# common_board_smd.net
KiCad netlist of a schematic drawn in EAGLE
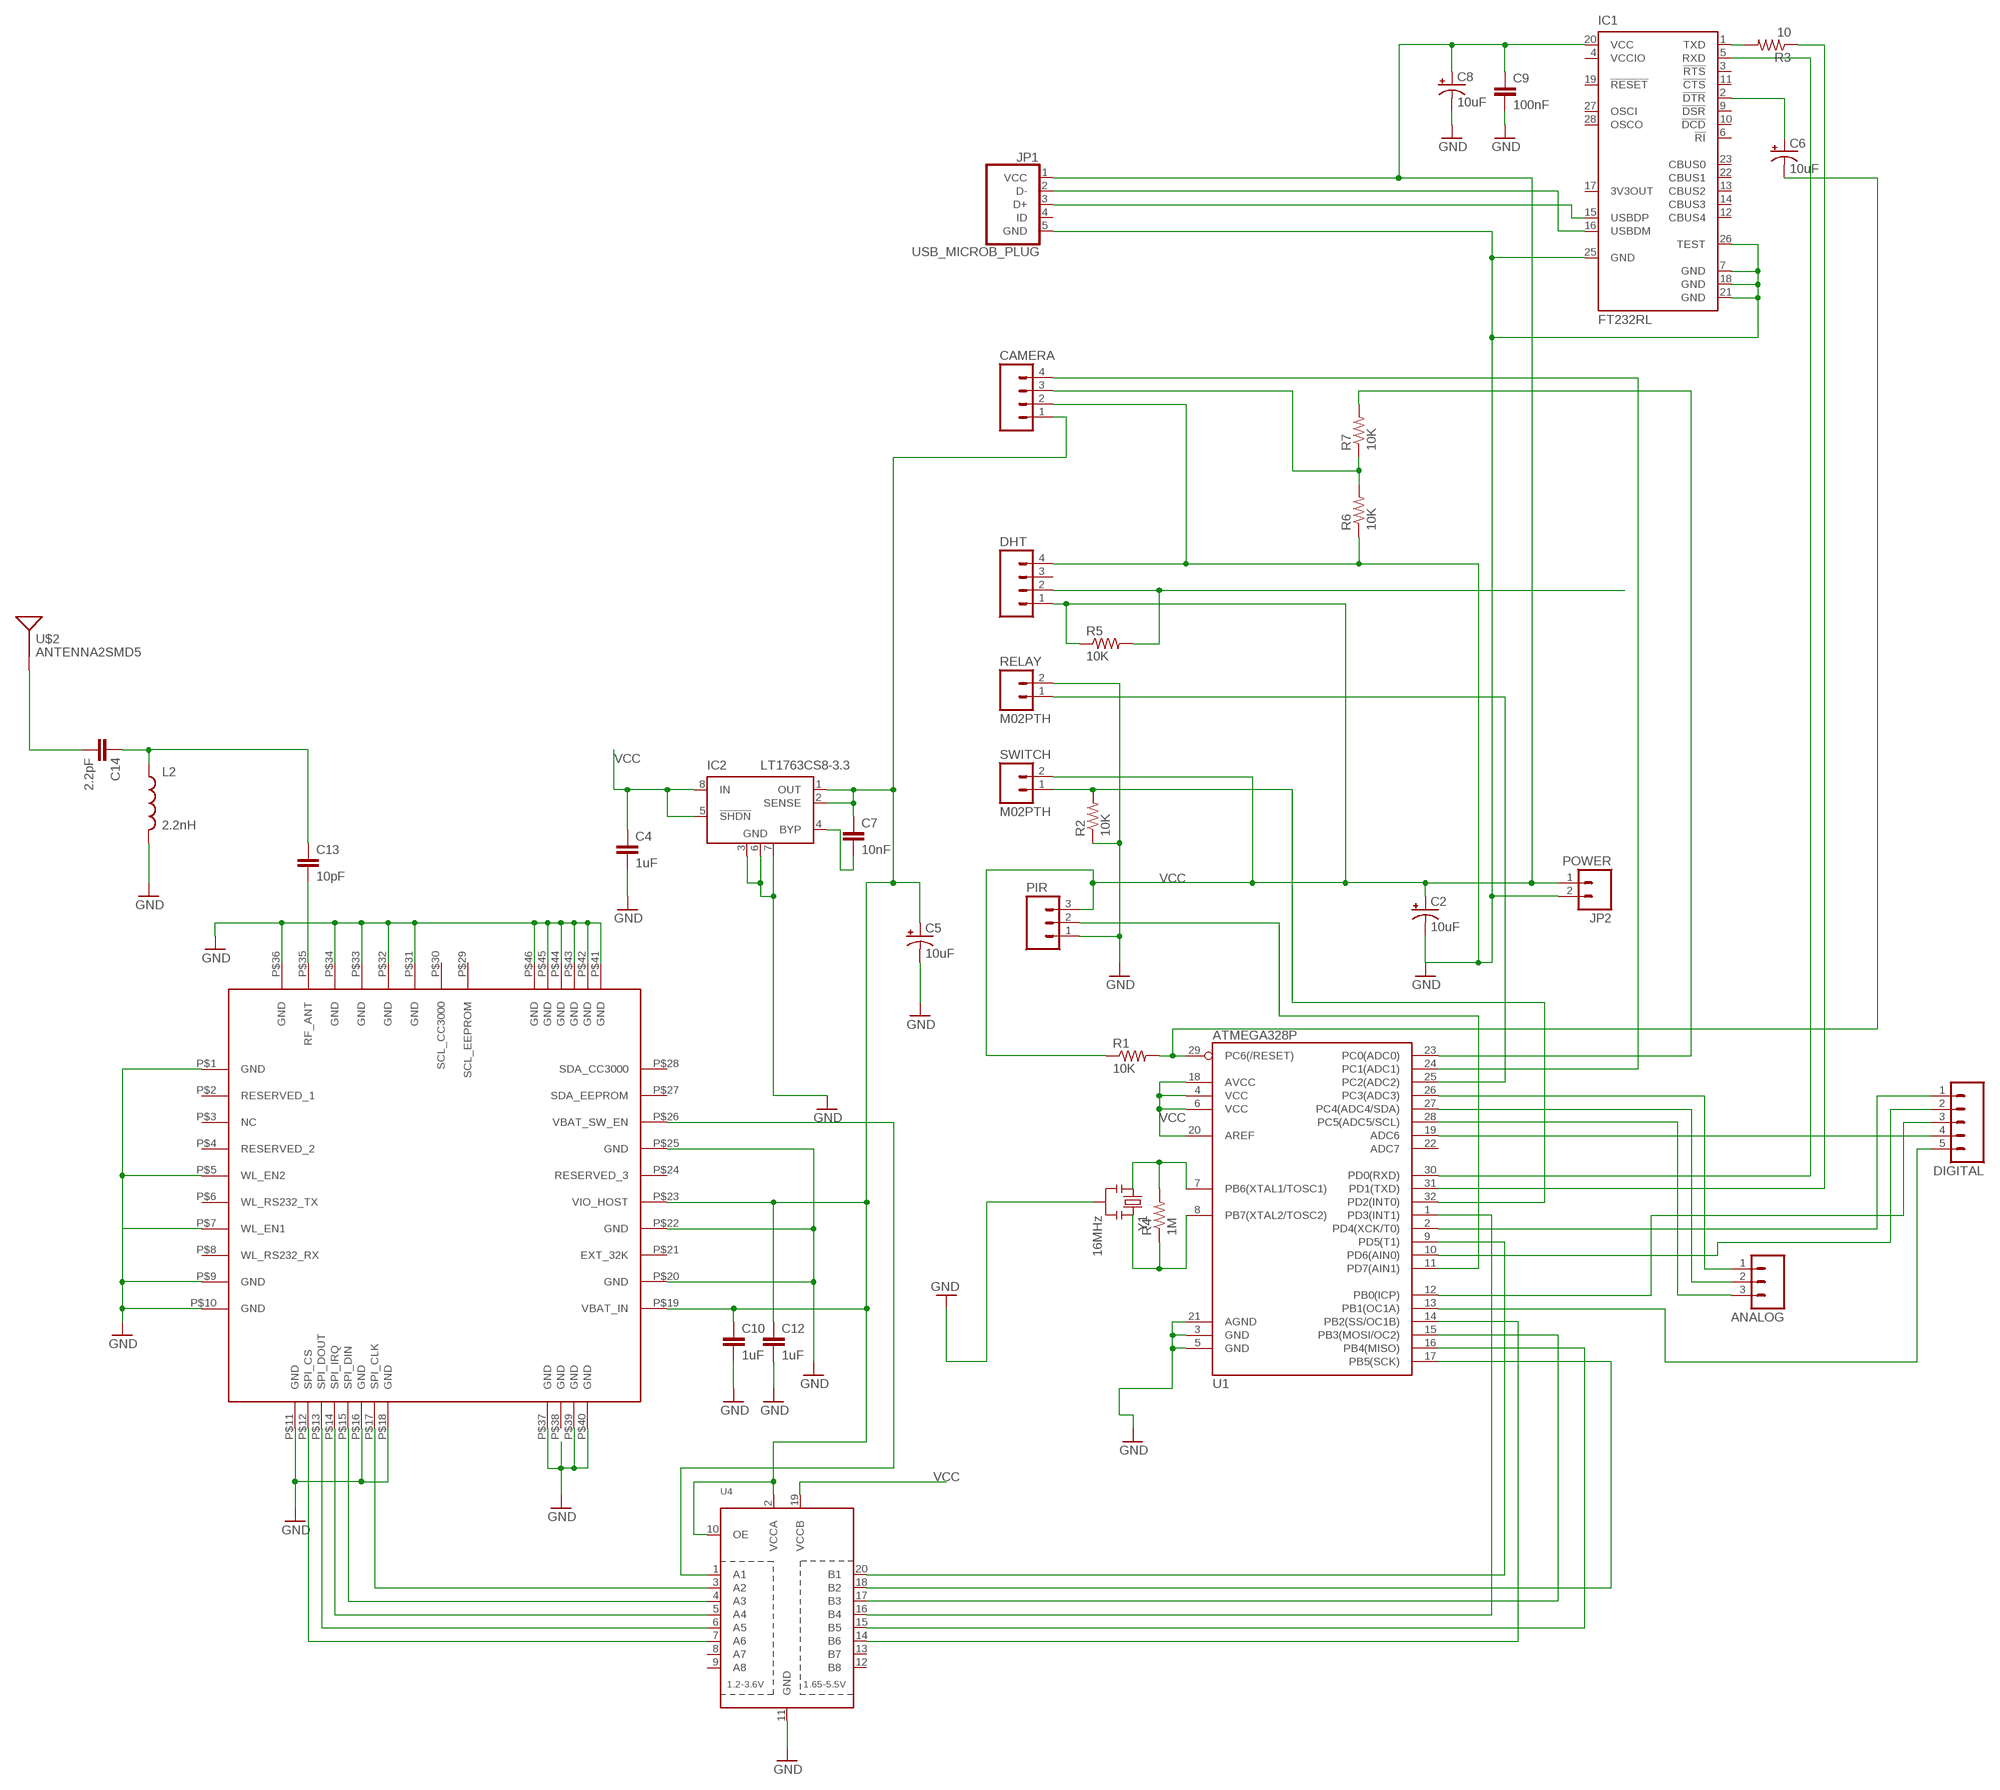
[diagram p0: schematic, sheet 1]

(export (version "E")
  (design (tool "Eeschema 10.0.6"))
  (components
    (comp (ref "ANALOG")
      (value "M03PTH")
      (footprint "eagle-import:1X03")
      (libsource (lib "eagle-import") (part "M03PTH"))
    )
    (comp (ref "C2")
      (value "10uF")
      (footprint "eagle-import:EIA3216")
      (libsource (lib "eagle-import") (part "CAP_POL1206"))
    )
    (comp (ref "C4")
      (value "1uF")
      (footprint "eagle-import:0805")
      (libsource (lib "eagle-import") (part "CAP0805"))
    )
    (comp (ref "C5")
      (value "10uF")
      (footprint "eagle-import:EIA3528")
      (libsource (lib "eagle-import") (part "CAP_POL3528"))
    )
    (comp (ref "C6")
      (value "10uF")
      (footprint "eagle-import:EIA3216")
      (libsource (lib "eagle-import") (part "CAP_POL1206"))
    )
    (comp (ref "C7")
      (value "10nF")
      (footprint "eagle-import:0805")
      (libsource (lib "eagle-import") (part "CAP0805"))
    )
    (comp (ref "C8")
      (value "10uF")
      (footprint "eagle-import:EIA3216")
      (libsource (lib "eagle-import") (part "CAP_POL1206"))
    )
    (comp (ref "C9")
      (value "100nF")
      (footprint "eagle-import:0805")
      (libsource (lib "eagle-import") (part "CAP0805"))
    )
    (comp (ref "C10")
      (value "1uF")
      (footprint "eagle-import:1206")
      (libsource (lib "eagle-import") (part "CAP1206"))
    )
    (comp (ref "C12")
      (value "1uF")
      (footprint "eagle-import:1206")
      (libsource (lib "eagle-import") (part "CAP1206"))
    )
    (comp (ref "C13")
      (value "10pF")
      (footprint "eagle-import:0805")
      (libsource (lib "eagle-import") (part "CAP0805"))
    )
    (comp (ref "C14")
      (value "2.2pF")
      (footprint "eagle-import:0805")
      (libsource (lib "eagle-import") (part "CAP0805"))
    )
    (comp (ref "CAMERA")
      (value "M04PTH")
      (footprint "eagle-import:1X04")
      (libsource (lib "eagle-import") (part "M04PTH"))
    )
    (comp (ref "DHT")
      (value "M04PTH")
      (footprint "eagle-import:1X04")
      (libsource (lib "eagle-import") (part "M04PTH"))
    )
    (comp (ref "DIGITAL")
      (value "M05PTH")
      (footprint "eagle-import:1X05")
      (libsource (lib "eagle-import") (part "M05PTH"))
    )
    (comp (ref "IC1")
      (value "FT232RL")
      (footprint "eagle-import:SSOP28")
      (libsource (lib "eagle-import") (part "FT232RL"))
    )
    (comp (ref "IC2")
      (value "LT1763CS8-3.3")
      (footprint "eagle-import:SOIC8")
      (libsource (lib "eagle-import") (part "LT1763CS8-3.3"))
    )
    (comp (ref "JP1")
      (value "USB_MICROB_PLUG")
      (footprint "eagle-import:MICRO-B-RA-SMT")
      (libsource (lib "eagle-import") (part "USB_MICROB_PLUG"))
    )
    (comp (ref "JP2")
      (value "POWER")
      (footprint "eagle-import:1X02")
      (libsource (lib "eagle-import") (part "M02PTH"))
    )
    (comp (ref "L2")
      (value "2.2nH")
      (footprint "eagle-import:0805")
      (libsource (lib "eagle-import") (part "INDUCTOR0805"))
    )
    (comp (ref "PIR")
      (value "M03PTH")
      (footprint "eagle-import:1X03")
      (libsource (lib "eagle-import") (part "M03PTH"))
    )
    (comp (ref "R1")
      (value "10K")
      (footprint "eagle-import:0805")
      (libsource (lib "eagle-import") (part "RESISTOR0805-RES"))
    )
    (comp (ref "R2")
      (value "10K")
      (footprint "eagle-import:0805")
      (libsource (lib "eagle-import") (part "RESISTOR0805-RES"))
    )
    (comp (ref "R3")
      (value "10")
      (footprint "eagle-import:0805")
      (libsource (lib "eagle-import") (part "RESISTOR0805-RES"))
    )
    (comp (ref "R4")
      (value "1M")
      (footprint "eagle-import:0603-RES")
      (libsource (lib "eagle-import") (part "SparkFun-Resistors_RESISTOR0603-RES"))
    )
    (comp (ref "R5")
      (value "10K")
      (footprint "eagle-import:0805")
      (libsource (lib "eagle-import") (part "RESISTOR0805-RES"))
    )
    (comp (ref "R6")
      (value "10K")
      (footprint "eagle-import:0805")
      (libsource (lib "eagle-import") (part "RESISTOR0805-RES"))
    )
    (comp (ref "R7")
      (value "10K")
      (footprint "eagle-import:0805")
      (libsource (lib "eagle-import") (part "RESISTOR0805-RES"))
    )
    (comp (ref "RELAY")
      (value "M02PTH")
      (footprint "eagle-import:1X02")
      (libsource (lib "eagle-import") (part "M02PTH"))
    )
    (comp (ref "SWITCH")
      (value "M02PTH")
      (footprint "eagle-import:1X02")
      (libsource (lib "eagle-import") (part "M02PTH"))
    )
    (comp (ref "U$1")
      (value "CC3000")
      (footprint "eagle-import:CC3000")
      (fields (field (name "AUTHOR") "Matt Bigarani"))
      (libsource (lib "eagle-import") (part "CC3000"))
    )
    (comp (ref "U$2")
      (value "ANTENNA2SMD5")
      (footprint "eagle-import:ANTENNA-CHIP5")
      (libsource (lib "eagle-import") (part "ANTENNA2SMD5"))
    )
    (comp (ref "U1")
      (value "ATMEGA328P")
      (footprint "eagle-import:TQFP32-08")
      (libsource (lib "eagle-import") (part "ATMEGA328_SMT"))
    )
    (comp (ref "U4")
      (value "TXB0108PWR")
      (footprint "eagle-import:TSSOP20")
      (libsource (lib "eagle-import") (part "TXB0108PWR"))
    )
    (comp (ref "Y1")
      (value "16MHz")
      (footprint "eagle-import:RESONATOR-SMD")
      (libsource (lib "eagle-import") (part "RESONATOR16MHZ"))
    )
  )
  (nets
    (net (code "1") (name "/SCL_CC3000") (class "Default")
      (node (ref "U$1") (pin "P$30") (pinfunction "SCL_CC3000_P$30") (pintype "power_in"))
    )
    (net (code "2") (name "/SCL_EEPROM") (class "Default")
      (node (ref "U$1") (pin "P$29") (pinfunction "SCL_EEPROM_P$29") (pintype "power_in"))
    )
    (net (code "3") (name "/VCC") (class "Default")
      (node (ref "C2") (pin "A") (pinfunction "+_A") (pintype "passive"))
      (node (ref "C4") (pin "1") (pinfunction "1_1") (pintype "passive"))
      (node (ref "C8") (pin "A") (pinfunction "+_A") (pintype "passive"))
      (node (ref "C9") (pin "1") (pinfunction "1_1") (pintype "passive"))
      (node (ref "DHT") (pin "1") (pinfunction "1_1") (pintype "passive"))
      (node (ref "IC1") (pin "20") (pinfunction "VCC_20") (pintype "power_in"))
      (node (ref "IC2") (pin "5") (pinfunction "~{SHDN}_5") (pintype "input"))
      (node (ref "IC2") (pin "8") (pinfunction "IN_8") (pintype "input"))
      (node (ref "JP1") (pin "1") (pinfunction "VCC_1") (pintype "bidirectional"))
      (node (ref "JP2") (pin "1") (pinfunction "1_1") (pintype "passive"))
      (node (ref "PIR") (pin "3") (pinfunction "3_3") (pintype "passive"))
      (node (ref "R1") (pin "1") (pinfunction "1_1") (pintype "passive"))
      (node (ref "R5") (pin "1") (pinfunction "1_1") (pintype "passive"))
      (node (ref "SWITCH") (pin "2") (pinfunction "2_2") (pintype "passive"))
      (node (ref "U1") (pin "18") (pinfunction "AVCC_18") (pintype "bidirectional"))
      (node (ref "U1") (pin "20") (pinfunction "AREF_20") (pintype "bidirectional"))
      (node (ref "U1") (pin "4") (pinfunction "VCC_4") (pintype "bidirectional"))
      (node (ref "U1") (pin "6") (pinfunction "VCC_6") (pintype "bidirectional"))
      (node (ref "U4") (pin "19") (pinfunction "VCCB_19") (pintype "bidirectional"))
    )
    (net (code "4") (name "/VCCIO") (class "Default")
      (node (ref "IC1") (pin "4") (pinfunction "VCCIO_4") (pintype "power_in"))
    )
    (net (code "5") (name "GND") (class "Default")
      (node (ref "C10") (pin "2") (pinfunction "2_2") (pintype "passive"))
      (node (ref "C12") (pin "2") (pinfunction "2_2") (pintype "passive"))
      (node (ref "C2") (pin "C") (pinfunction "-_C") (pintype "passive"))
      (node (ref "C4") (pin "2") (pinfunction "2_2") (pintype "passive"))
      (node (ref "C5") (pin "C") (pinfunction "-_C") (pintype "passive"))
      (node (ref "C8") (pin "C") (pinfunction "-_C") (pintype "passive"))
      (node (ref "C9") (pin "2") (pinfunction "2_2") (pintype "passive"))
      (node (ref "CAMERA") (pin "2") (pinfunction "2_2") (pintype "passive"))
      (node (ref "DHT") (pin "4") (pinfunction "4_4") (pintype "passive"))
      (node (ref "IC1") (pin "18") (pinfunction "GND_18") (pintype "power_in"))
      (node (ref "IC1") (pin "21") (pinfunction "GND_21") (pintype "power_in"))
      (node (ref "IC1") (pin "25") (pinfunction "GND_25") (pintype "power_in"))
      (node (ref "IC1") (pin "26") (pinfunction "TEST_26") (pintype "input"))
      (node (ref "IC1") (pin "7") (pinfunction "GND_7") (pintype "power_in"))
      (node (ref "IC2") (pin "3") (pinfunction "GND_3") (pintype "power_in"))
      (node (ref "IC2") (pin "6") (pinfunction "GND_6") (pintype "power_in"))
      (node (ref "IC2") (pin "7") (pinfunction "GND_7") (pintype "power_in"))
      (node (ref "JP1") (pin "5") (pinfunction "GND_5") (pintype "bidirectional"))
      (node (ref "JP2") (pin "2") (pinfunction "2_2") (pintype "passive"))
      (node (ref "L2") (pin "2") (pinfunction "2_2") (pintype "passive"))
      (node (ref "PIR") (pin "1") (pinfunction "1_1") (pintype "passive"))
      (node (ref "R2") (pin "1") (pinfunction "1_1") (pintype "passive"))
      (node (ref "R6") (pin "1") (pinfunction "1_1") (pintype "passive"))
      (node (ref "RELAY") (pin "2") (pinfunction "2_2") (pintype "passive"))
      (node (ref "U$1") (pin "P$1") (pinfunction "GND_P$1") (pintype "power_in"))
      (node (ref "U$1") (pin "P$10") (pinfunction "GND_P$10") (pintype "power_in"))
      (node (ref "U$1") (pin "P$11") (pinfunction "GND_P$11") (pintype "power_in"))
      (node (ref "U$1") (pin "P$16") (pinfunction "GND_P$16") (pintype "power_in"))
      (node (ref "U$1") (pin "P$18") (pinfunction "GND_P$18") (pintype "power_in"))
      (node (ref "U$1") (pin "P$20") (pinfunction "GND_P$20") (pintype "bidirectional"))
      (node (ref "U$1") (pin "P$22") (pinfunction "GND_P$22") (pintype "bidirectional"))
      (node (ref "U$1") (pin "P$25") (pinfunction "GND_P$25") (pintype "bidirectional"))
      (node (ref "U$1") (pin "P$31") (pinfunction "GND_P$31") (pintype "power_in"))
      (node (ref "U$1") (pin "P$32") (pinfunction "GND_P$32") (pintype "power_in"))
      (node (ref "U$1") (pin "P$33") (pinfunction "GND_P$33") (pintype "power_in"))
      (node (ref "U$1") (pin "P$34") (pinfunction "GND_P$34") (pintype "power_in"))
      (node (ref "U$1") (pin "P$36") (pinfunction "GND_P$36") (pintype "passive"))
      (node (ref "U$1") (pin "P$37") (pinfunction "GND_P$37") (pintype "power_in"))
      (node (ref "U$1") (pin "P$39") (pinfunction "GND_P$39") (pintype "power_in"))
      (node (ref "U$1") (pin "P$40") (pinfunction "GND_P$40") (pintype "power_in"))
      (node (ref "U$1") (pin "P$41") (pinfunction "GND_P$41") (pintype "power_in"))
      (node (ref "U$1") (pin "P$42") (pinfunction "GND_P$42") (pintype "power_in"))
      (node (ref "U$1") (pin "P$43") (pinfunction "GND_P$43") (pintype "power_in"))
      (node (ref "U$1") (pin "P$44") (pinfunction "GND_P$44") (pintype "power_in"))
      (node (ref "U$1") (pin "P$45") (pinfunction "GND_P$45") (pintype "power_in"))
      (node (ref "U$1") (pin "P$46") (pinfunction "GND_P$46") (pintype "power_in"))
      (node (ref "U$1") (pin "P$5") (pinfunction "WL_EN2_P$5") (pintype "bidirectional"))
      (node (ref "U$1") (pin "P$7") (pinfunction "WL_EN1_P$7") (pintype "bidirectional"))
      (node (ref "U$1") (pin "P$9") (pinfunction "GND_P$9") (pintype "bidirectional"))
      (node (ref "U1") (pin "21") (pinfunction "AGND_21") (pintype "bidirectional"))
      (node (ref "U1") (pin "3") (pinfunction "GND_3") (pintype "bidirectional"))
      (node (ref "U1") (pin "5") (pinfunction "GND_5") (pintype "bidirectional"))
      (node (ref "U4") (pin "11") (pinfunction "GND_11") (pintype "bidirectional"))
      (node (ref "Y1") (pin "2") (pinfunction "2_2") (pintype "passive"))
    )
    (net (code "6") (name "Net-(C5-+)") (class "Default")
      (node (ref "C10") (pin "1") (pinfunction "1_1") (pintype "passive"))
      (node (ref "C12") (pin "1") (pinfunction "1_1") (pintype "passive"))
      (node (ref "C5") (pin "A") (pinfunction "+_A") (pintype "passive"))
      (node (ref "C7") (pin "1") (pinfunction "1_1") (pintype "passive"))
      (node (ref "CAMERA") (pin "1") (pinfunction "1_1") (pintype "passive"))
      (node (ref "IC2") (pin "1") (pinfunction "OUT_1") (pintype "passive"))
      (node (ref "IC2") (pin "2") (pinfunction "SENSE_2") (pintype "input"))
      (node (ref "U$1") (pin "P$19") (pinfunction "VBAT_IN_P$19") (pintype "bidirectional"))
      (node (ref "U$1") (pin "P$23") (pinfunction "VIO_HOST_P$23") (pintype "bidirectional"))
      (node (ref "U4") (pin "10") (pinfunction "OE_10") (pintype "bidirectional"))
      (node (ref "U4") (pin "2") (pinfunction "VCCA_2") (pintype "bidirectional"))
    )
    (net (code "7") (name "Net-(C6-+)") (class "Default")
      (node (ref "C6") (pin "A") (pinfunction "+_A") (pintype "passive"))
      (node (ref "IC1") (pin "2") (pinfunction "~{DTR}_2") (pintype "output"))
    )
    (net (code "8") (name "Net-(C6--)") (class "Default")
      (node (ref "C6") (pin "C") (pinfunction "-_C") (pintype "passive"))
      (node (ref "R1") (pin "2") (pinfunction "2_2") (pintype "passive"))
      (node (ref "U1") (pin "29") (pinfunction "PC6(/RESET)_29") (pintype "bidirectional"))
    )
    (net (code "9") (name "Net-(C13-Pad1)") (class "Default")
      (node (ref "C13") (pin "1") (pinfunction "1_1") (pintype "passive"))
      (node (ref "C14") (pin "1") (pinfunction "1_1") (pintype "passive"))
      (node (ref "L2") (pin "1") (pinfunction "1_1") (pintype "passive"))
    )
    (net (code "10") (name "Net-(CAMERA-Pad3)") (class "Default")
      (node (ref "CAMERA") (pin "3") (pinfunction "3_3") (pintype "passive"))
      (node (ref "R6") (pin "2") (pinfunction "2_2") (pintype "passive"))
      (node (ref "R7") (pin "1") (pinfunction "1_1") (pintype "passive"))
    )
    (net (code "11") (name "Net-(DHT-Pad2)") (class "Default")
      (node (ref "DHT") (pin "2") (pinfunction "2_2") (pintype "passive"))
      (node (ref "R5") (pin "2") (pinfunction "2_2") (pintype "passive"))
    )
    (net (code "12") (name "Net-(IC1-RXD)") (class "Default")
      (node (ref "IC1") (pin "5") (pinfunction "RXD_5") (pintype "input"))
      (node (ref "U1") (pin "30") (pinfunction "PD0(RXD)_30") (pintype "bidirectional"))
    )
    (net (code "13") (name "Net-(IC1-TXD)") (class "Default")
      (node (ref "IC1") (pin "1") (pinfunction "TXD_1") (pintype "output"))
      (node (ref "R3") (pin "2") (pinfunction "2_2") (pintype "passive"))
    )
    (net (code "14") (name "Net-(IC1-USBDM)") (class "Default")
      (node (ref "IC1") (pin "16") (pinfunction "USBDM_16") (pintype "bidirectional"))
      (node (ref "JP1") (pin "2") (pinfunction "D-_2") (pintype "bidirectional"))
    )
    (net (code "15") (name "Net-(IC1-USBDP)") (class "Default")
      (node (ref "IC1") (pin "15") (pinfunction "USBDP_15") (pintype "bidirectional"))
      (node (ref "JP1") (pin "3") (pinfunction "D+_3") (pintype "bidirectional"))
    )
    (net (code "16") (name "Net-(IC2-BYP)") (class "Default")
      (node (ref "C7") (pin "2") (pinfunction "2_2") (pintype "passive"))
      (node (ref "IC2") (pin "4") (pinfunction "BYP_4") (pintype "input"))
    )
    (net (code "17") (name "Net-(U$1-RF_ANT)") (class "Default")
      (node (ref "C13") (pin "2") (pinfunction "2_2") (pintype "passive"))
      (node (ref "U$1") (pin "P$35") (pinfunction "RF_ANT_P$35") (pintype "bidirectional"))
    )
    (net (code "18") (name "Net-(U$1-SPI_CLK)") (class "Default")
      (node (ref "U$1") (pin "P$17") (pinfunction "SPI_CLK_P$17") (pintype "bidirectional"))
      (node (ref "U4") (pin "3") (pinfunction "A2_3") (pintype "bidirectional"))
    )
    (net (code "19") (name "Net-(U$1-SPI_CS)") (class "Default")
      (node (ref "U$1") (pin "P$12") (pinfunction "SPI_CS_P$12") (pintype "bidirectional"))
      (node (ref "U4") (pin "7") (pinfunction "A6_7") (pintype "bidirectional"))
    )
    (net (code "20") (name "Net-(U$1-SPI_DIN)") (class "Default")
      (node (ref "U$1") (pin "P$15") (pinfunction "SPI_DIN_P$15") (pintype "bidirectional"))
      (node (ref "U4") (pin "4") (pinfunction "A3_4") (pintype "bidirectional"))
    )
    (net (code "21") (name "Net-(U$1-SPI_DOUT)") (class "Default")
      (node (ref "U$1") (pin "P$13") (pinfunction "SPI_DOUT_P$13") (pintype "bidirectional"))
      (node (ref "U4") (pin "6") (pinfunction "A5_6") (pintype "bidirectional"))
    )
    (net (code "22") (name "Net-(U$1-SPI_IRQ)") (class "Default")
      (node (ref "U$1") (pin "P$14") (pinfunction "SPI_IRQ_P$14") (pintype "bidirectional"))
      (node (ref "U4") (pin "5") (pinfunction "A4_5") (pintype "bidirectional"))
    )
    (net (code "23") (name "Net-(U$1-VBAT_SW_EN)") (class "Default")
      (node (ref "U$1") (pin "P$26") (pinfunction "VBAT_SW_EN_P$26") (pintype "bidirectional"))
      (node (ref "U4") (pin "1") (pinfunction "A1_1") (pintype "bidirectional"))
    )
    (net (code "24") (name "Net-(U$2-SIGNAL)") (class "Default")
      (node (ref "C14") (pin "2") (pinfunction "2_2") (pintype "passive"))
      (node (ref "U$2") (pin "FEED") (pinfunction "SIGNAL_FEED") (pintype "bidirectional"))
    )
    (net (code "25") (name "Net-(U1-ADC6)") (class "Default")
      (node (ref "DIGITAL") (pin "4") (pinfunction "4_4") (pintype "passive"))
      (node (ref "U1") (pin "19") (pinfunction "ADC6_19") (pintype "bidirectional"))
    )
    (net (code "26") (name "Net-(U1-PB0(ICP))") (class "Default")
      (node (ref "DIGITAL") (pin "3") (pinfunction "3_3") (pintype "passive"))
      (node (ref "U1") (pin "12") (pinfunction "PB0(ICP)_12") (pintype "bidirectional"))
    )
    (net (code "27") (name "Net-(U1-PB1(OC1A))") (class "Default")
      (node (ref "DIGITAL") (pin "5") (pinfunction "5_5") (pintype "passive"))
      (node (ref "U1") (pin "13") (pinfunction "PB1(OC1A)_13") (pintype "bidirectional"))
    )
    (net (code "28") (name "Net-(U1-PB2(SS{slash}OC1B))") (class "Default")
      (node (ref "U1") (pin "14") (pinfunction "PB2(SS/OC1B)_14") (pintype "bidirectional"))
      (node (ref "U4") (pin "14") (pinfunction "B6_14") (pintype "bidirectional"))
    )
    (net (code "29") (name "Net-(U1-PB3(MOSI{slash}OC2))") (class "Default")
      (node (ref "U1") (pin "15") (pinfunction "PB3(MOSI/OC2)_15") (pintype "bidirectional"))
      (node (ref "U4") (pin "17") (pinfunction "B3_17") (pintype "bidirectional"))
    )
    (net (code "30") (name "Net-(U1-PB4(MISO))") (class "Default")
      (node (ref "U1") (pin "16") (pinfunction "PB4(MISO)_16") (pintype "bidirectional"))
      (node (ref "U4") (pin "15") (pinfunction "B5_15") (pintype "bidirectional"))
    )
    (net (code "31") (name "Net-(U1-PB5(SCK))") (class "Default")
      (node (ref "U1") (pin "17") (pinfunction "PB5(SCK)_17") (pintype "bidirectional"))
      (node (ref "U4") (pin "18") (pinfunction "B2_18") (pintype "bidirectional"))
    )
    (net (code "32") (name "Net-(U1-PB6(XTAL1{slash}TOSC1))") (class "Default")
      (node (ref "R4") (pin "2") (pinfunction "2_2") (pintype "passive"))
      (node (ref "U1") (pin "7") (pinfunction "PB6(XTAL1/TOSC1)_7") (pintype "bidirectional"))
      (node (ref "Y1") (pin "1") (pinfunction "1_1") (pintype "passive"))
    )
    (net (code "33") (name "Net-(U1-PB7(XTAL2{slash}TOSC2))") (class "Default")
      (node (ref "R4") (pin "1") (pinfunction "1_1") (pintype "passive"))
      (node (ref "U1") (pin "8") (pinfunction "PB7(XTAL2/TOSC2)_8") (pintype "bidirectional"))
      (node (ref "Y1") (pin "3") (pinfunction "3_3") (pintype "passive"))
    )
    (net (code "34") (name "Net-(U1-PC0(ADC0))") (class "Default")
      (node (ref "R7") (pin "2") (pinfunction "2_2") (pintype "passive"))
      (node (ref "U1") (pin "23") (pinfunction "PC0(ADC0)_23") (pintype "bidirectional"))
    )
    (net (code "35") (name "Net-(U1-PC1(ADC1))") (class "Default")
      (node (ref "CAMERA") (pin "4") (pinfunction "4_4") (pintype "passive"))
      (node (ref "U1") (pin "24") (pinfunction "PC1(ADC1)_24") (pintype "bidirectional"))
    )
    (net (code "36") (name "Net-(U1-PC2(ADC2))") (class "Default")
      (node (ref "RELAY") (pin "1") (pinfunction "1_1") (pintype "passive"))
      (node (ref "U1") (pin "25") (pinfunction "PC2(ADC2)_25") (pintype "bidirectional"))
    )
    (net (code "37") (name "Net-(U1-PC3(ADC3))") (class "Default")
      (node (ref "ANALOG") (pin "1") (pinfunction "1_1") (pintype "passive"))
      (node (ref "U1") (pin "26") (pinfunction "PC3(ADC3)_26") (pintype "bidirectional"))
    )
    (net (code "38") (name "Net-(U1-PC4(ADC4{slash}SDA))") (class "Default")
      (node (ref "ANALOG") (pin "2") (pinfunction "2_2") (pintype "passive"))
      (node (ref "U1") (pin "27") (pinfunction "PC4(ADC4/SDA)_27") (pintype "bidirectional"))
    )
    (net (code "39") (name "Net-(U1-PC5(ADC5{slash}SCL))") (class "Default")
      (node (ref "ANALOG") (pin "3") (pinfunction "3_3") (pintype "passive"))
      (node (ref "U1") (pin "28") (pinfunction "PC5(ADC5/SCL)_28") (pintype "bidirectional"))
    )
    (net (code "40") (name "Net-(U1-PD1(TXD))") (class "Default")
      (node (ref "R3") (pin "1") (pinfunction "1_1") (pintype "passive"))
      (node (ref "U1") (pin "31") (pinfunction "PD1(TXD)_31") (pintype "bidirectional"))
    )
    (net (code "41") (name "Net-(U1-PD2(INT0))") (class "Default")
      (node (ref "R2") (pin "2") (pinfunction "2_2") (pintype "passive"))
      (node (ref "SWITCH") (pin "1") (pinfunction "1_1") (pintype "passive"))
      (node (ref "U1") (pin "32") (pinfunction "PD2(INT0)_32") (pintype "bidirectional"))
    )
    (net (code "42") (name "Net-(U1-PD3(INT1))") (class "Default")
      (node (ref "U1") (pin "1") (pinfunction "PD3(INT1)_1") (pintype "bidirectional"))
      (node (ref "U4") (pin "16") (pinfunction "B4_16") (pintype "bidirectional"))
    )
    (net (code "43") (name "Net-(U1-PD4(XCK{slash}T0))") (class "Default")
      (node (ref "DIGITAL") (pin "1") (pinfunction "1_1") (pintype "passive"))
      (node (ref "U1") (pin "2") (pinfunction "PD4(XCK/T0)_2") (pintype "bidirectional"))
    )
    (net (code "44") (name "Net-(U1-PD5(T1))") (class "Default")
      (node (ref "U1") (pin "9") (pinfunction "PD5(T1)_9") (pintype "bidirectional"))
      (node (ref "U4") (pin "20") (pinfunction "B1_20") (pintype "bidirectional"))
    )
    (net (code "45") (name "Net-(U1-PD6(AIN0))") (class "Default")
      (node (ref "DIGITAL") (pin "2") (pinfunction "2_2") (pintype "passive"))
      (node (ref "U1") (pin "10") (pinfunction "PD6(AIN0)_10") (pintype "bidirectional"))
    )
    (net (code "46") (name "Net-(U1-PD7(AIN1))") (class "Default")
      (node (ref "PIR") (pin "2") (pinfunction "2_2") (pintype "passive"))
      (node (ref "U1") (pin "11") (pinfunction "PD7(AIN1)_11") (pintype "bidirectional"))
    )
    (net (code "47") (name "unconnected-(DHT-Pad3)") (class "Default")
      (node (ref "DHT") (pin "3") (pinfunction "3_3") (pintype "passive"))
    )
    (net (code "48") (name "unconnected-(IC1-3V3OUT-Pad17)") (class "Default")
      (node (ref "IC1") (pin "17") (pinfunction "3V3OUT_17") (pintype "output"))
    )
    (net (code "49") (name "unconnected-(IC1-CBUS0-Pad23)") (class "Default")
      (node (ref "IC1") (pin "23") (pinfunction "CBUS0_23") (pintype "bidirectional"))
    )
    (net (code "50") (name "unconnected-(IC1-CBUS1-Pad22)") (class "Default")
      (node (ref "IC1") (pin "22") (pinfunction "CBUS1_22") (pintype "bidirectional"))
    )
    (net (code "51") (name "unconnected-(IC1-CBUS2-Pad13)") (class "Default")
      (node (ref "IC1") (pin "13") (pinfunction "CBUS2_13") (pintype "bidirectional"))
    )
    (net (code "52") (name "unconnected-(IC1-CBUS3-Pad14)") (class "Default")
      (node (ref "IC1") (pin "14") (pinfunction "CBUS3_14") (pintype "bidirectional"))
    )
    (net (code "53") (name "unconnected-(IC1-CBUS4-Pad12)") (class "Default")
      (node (ref "IC1") (pin "12") (pinfunction "CBUS4_12") (pintype "bidirectional"))
    )
    (net (code "54") (name "unconnected-(IC1-OSCI-Pad27)") (class "Default")
      (node (ref "IC1") (pin "27") (pinfunction "OSCI_27") (pintype "input"))
    )
    (net (code "55") (name "unconnected-(IC1-OSCO-Pad28)") (class "Default")
      (node (ref "IC1") (pin "28") (pinfunction "OSCO_28") (pintype "output"))
    )
    (net (code "56") (name "unconnected-(IC1-~{CTS}-Pad11)") (class "Default")
      (node (ref "IC1") (pin "11") (pinfunction "~{CTS}_11") (pintype "input"))
    )
    (net (code "57") (name "unconnected-(IC1-~{DCD}-Pad10)") (class "Default")
      (node (ref "IC1") (pin "10") (pinfunction "~{DCD}_10") (pintype "input"))
    )
    (net (code "58") (name "unconnected-(IC1-~{DSR}-Pad9)") (class "Default")
      (node (ref "IC1") (pin "9") (pinfunction "~{DSR}_9") (pintype "input"))
    )
    (net (code "59") (name "unconnected-(IC1-~{RESET}-Pad19)") (class "Default")
      (node (ref "IC1") (pin "19") (pinfunction "~{RESET}_19") (pintype "input"))
    )
    (net (code "60") (name "unconnected-(IC1-~{RI}-Pad6)") (class "Default")
      (node (ref "IC1") (pin "6") (pinfunction "~{RI}_6") (pintype "input"))
    )
    (net (code "61") (name "unconnected-(IC1-~{RTS}-Pad3)") (class "Default")
      (node (ref "IC1") (pin "3") (pinfunction "~{RTS}_3") (pintype "output"))
    )
    (net (code "62") (name "unconnected-(JP1-ID-Pad4)") (class "Default")
      (node (ref "JP1") (pin "4") (pinfunction "ID_4") (pintype "bidirectional"))
    )
    (net (code "63") (name "unconnected-(U$1-EXT_32K-PadP$21)") (class "Default")
      (node (ref "U$1") (pin "P$21") (pinfunction "EXT_32K_P$21") (pintype "bidirectional"))
    )
    (net (code "64") (name "unconnected-(U$1-GND-PadP$38)") (class "Default")
      (node (ref "U$1") (pin "P$38") (pinfunction "GND_P$38") (pintype "passive"))
    )
    (net (code "65") (name "unconnected-(U$1-NC-PadP$3)") (class "Default")
      (node (ref "U$1") (pin "P$3") (pinfunction "NC_P$3") (pintype "no_connect"))
    )
    (net (code "66") (name "unconnected-(U$1-RESERVED_1-PadP$2)") (class "Default")
      (node (ref "U$1") (pin "P$2") (pinfunction "RESERVED_1_P$2") (pintype "bidirectional"))
    )
    (net (code "67") (name "unconnected-(U$1-RESERVED_2-PadP$4)") (class "Default")
      (node (ref "U$1") (pin "P$4") (pinfunction "RESERVED_2_P$4") (pintype "bidirectional"))
    )
    (net (code "68") (name "unconnected-(U$1-RESERVED_3-PadP$24)") (class "Default")
      (node (ref "U$1") (pin "P$24") (pinfunction "RESERVED_3_P$24") (pintype "bidirectional"))
    )
    (net (code "69") (name "unconnected-(U$1-SDA_CC3000-PadP$28)") (class "Default")
      (node (ref "U$1") (pin "P$28") (pinfunction "SDA_CC3000_P$28") (pintype "bidirectional"))
    )
    (net (code "70") (name "unconnected-(U$1-SDA_EEPROM-PadP$27)") (class "Default")
      (node (ref "U$1") (pin "P$27") (pinfunction "SDA_EEPROM_P$27") (pintype "bidirectional"))
    )
    (net (code "71") (name "unconnected-(U$1-WL_RS232_RX-PadP$8)") (class "Default")
      (node (ref "U$1") (pin "P$8") (pinfunction "WL_RS232_RX_P$8") (pintype "bidirectional"))
    )
    (net (code "72") (name "unconnected-(U$1-WL_RS232_TX-PadP$6)") (class "Default")
      (node (ref "U$1") (pin "P$6") (pinfunction "WL_RS232_TX_P$6") (pintype "bidirectional"))
    )
    (net (code "73") (name "unconnected-(U1-ADC7-Pad22)") (class "Default")
      (node (ref "U1") (pin "22") (pinfunction "ADC7_22") (pintype "bidirectional"))
    )
    (net (code "74") (name "unconnected-(U4-A7-Pad8)") (class "Default")
      (node (ref "U4") (pin "8") (pinfunction "A7_8") (pintype "bidirectional"))
    )
    (net (code "75") (name "unconnected-(U4-A8-Pad9)") (class "Default")
      (node (ref "U4") (pin "9") (pinfunction "A8_9") (pintype "bidirectional"))
    )
    (net (code "76") (name "unconnected-(U4-B7-Pad13)") (class "Default")
      (node (ref "U4") (pin "13") (pinfunction "B7_13") (pintype "bidirectional"))
    )
    (net (code "77") (name "unconnected-(U4-B8-Pad12)") (class "Default")
      (node (ref "U4") (pin "12") (pinfunction "B8_12") (pintype "bidirectional"))
    )
  )
)
